# config_battery.net
KiCad netlist of a schematic drawn in Altium Designer
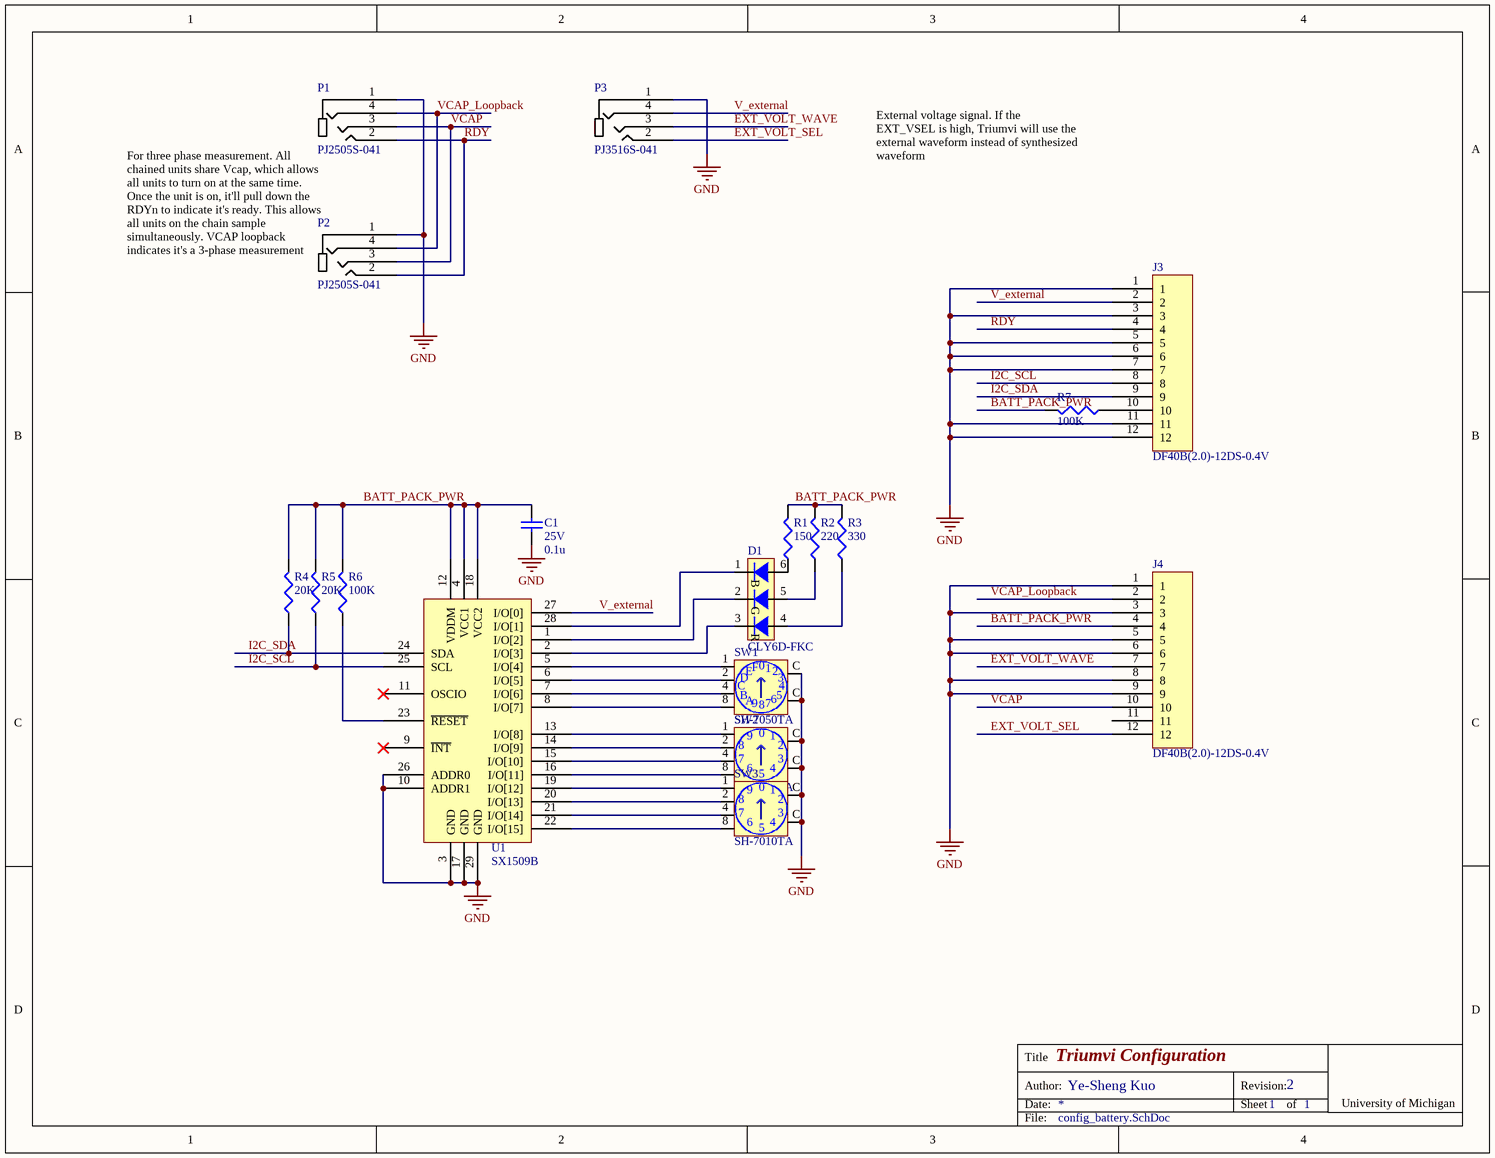
[diagram p0: config_battery.SchDoc]

(export (version "E")
  (design (tool "Eeschema 10.0.6"))
  (components
    (comp (ref "C1")
      (value "0.1u")
      (footprint "0603")
      (description "Ceramic capacitor, 0.1 uF, 0603 package")
      (fields
        (field (name "VOLTAGE RATED") "25V")
        (field (name "TOLERANCE") "10%")
        (field (name "Comment") "Ceramic capacitor")
      )
      (libsource (lib "rlc") (part "C_0.1u_25V_0603_ceramic"))
    )
    (comp (ref "D1")
      (value "CLY6D-FKC")
      (footprint "PLCC6")
      (description "CREE PLCC6 3 in 1 SMD LED")
      (libsource (lib "rlc") (part "D_CLY6D-FKC"))
    )
    (comp (ref "J3")
      (value "DF40B(2.0)-12DS-0.4V")
      (footprint "DF40B(2.0)-12DS-0.4V")
      (description "Hirose BM20 Series, 0.4mm pitch, 2mm stack height, 12 pos, header")
      (libsource (lib "connectors") (part "DF40B(2.0)-12DS-0.4V"))
    )
    (comp (ref "J4")
      (value "DF40B(2.0)-12DS-0.4V")
      (footprint "DF40B(2.0)-12DS-0.4V")
      (description "Hirose BM20 Series, 0.4mm pitch, 2mm stack height, 12 pos, header")
      (libsource (lib "connectors") (part "DF40B(2.0)-12DS-0.4V"))
    )
    (comp (ref "P1")
      (value "PJ2505S-041")
      (footprint "PJ2505S-041")
      (description "2.5 mm phone jack, 4 terminals")
      (libsource (lib "connectors") (part "PJ2505S-041"))
    )
    (comp (ref "P2")
      (value "PJ2505S-041")
      (footprint "PJ2505S-041")
      (description "2.5 mm phone jack, 4 terminals")
      (libsource (lib "connectors") (part "PJ2505S-041"))
    )
    (comp (ref "P3")
      (value "PJ3516S-041")
      (footprint "PJ3516S-041")
      (description "3.5 mm phone jack, 4 terminals")
      (libsource (lib "connectors") (part "PJ3516S-041"))
    )
    (comp (ref "R1")
      (value "150")
      (footprint "0603")
      (description "Chip resistor, 150,  0603 package")
      (fields (field (name "TOLERANCE") "1%") (field (name "POWER") "1/1 W"))
      (libsource (lib "rlc") (part "R_150_0603"))
    )
    (comp (ref "R2")
      (value "220")
      (footprint "0603")
      (description "Chip resistor, 220, 0603 package")
      (fields (field (name "TOLERANCE") "1%") (field (name "POWER") "1/10 W"))
      (libsource (lib "rlc") (part "R_220_0603"))
    )
    (comp (ref "R3")
      (value "330")
      (footprint "0603")
      (description "Chip resistor, 330, 0603 package")
      (fields (field (name "TOLERANCE") "1%") (field (name "POWER") "1/10 W"))
      (libsource (lib "rlc") (part "R_330_0603"))
    )
    (comp (ref "R4")
      (value "20K")
      (footprint "0603")
      (description "Chip resistor, 20K, 0603 package")
      (fields (field (name "TOLERANCE") "1%") (field (name "POWER") "1/10 W"))
      (libsource (lib "rlc") (part "R_20K_0603"))
    )
    (comp (ref "R5")
      (value "20K")
      (footprint "0603")
      (description "Chip resistor, 20K, 0603 package")
      (fields (field (name "TOLERANCE") "1%") (field (name "POWER") "1/10 W"))
      (libsource (lib "rlc") (part "R_20K_0603"))
    )
    (comp (ref "R6")
      (value "100K")
      (footprint "0603")
      (description "Chip resistor, 100K, 0603 package")
      (fields (field (name "TOLERANCE") "1%") (field (name "POWER") "1/10 W"))
      (libsource (lib "rlc") (part "R_100K_0603"))
    )
    (comp (ref "R7")
      (value "100K")
      (footprint "0603")
      (description "Chip resistor, 100K, 0603 package")
      (fields (field (name "TOLERANCE") "1%") (field (name "POWER") "1/10 W"))
      (libsource (lib "rlc") (part "R_100K_0603"))
    )
    (comp (ref "SW1")
      (value "SH-7050TA")
      (footprint "SH-7050A")
      (description "ROTARY CODED SWITCHES")
      (libsource (lib "switches") (part "SH-7050TA"))
    )
    (comp (ref "SW2")
      (value "SH-7010TA")
      (footprint "SH-7010A")
      (description "ROTARY CODED SWITCHES")
      (libsource (lib "switches") (part "SH-7010TA"))
    )
    (comp (ref "SW3")
      (value "SH-7010TA")
      (footprint "SH-7010A")
      (description "ROTARY CODED SWITCHES")
      (libsource (lib "switches") (part "SH-7010TA"))
    )
    (comp (ref "U1")
      (value "SX1509B")
      (footprint "QFN40P400X400X60_HS-29N")
      (description "Voltage Level Shifting GPIO  with LED Driver and Keypad Engine")
      (libsource (lib "io_expansion") (part "SX1509B"))
    )
  )
  (nets
    (net (code "1") (name "/BATT_PACK_PWR") (class "Default")
      (node (ref "C1") (pin "1") (pintype "passive"))
      (node (ref "J4") (pin "4") (pinfunction "4_4") (pintype "passive"))
      (node (ref "R1") (pin "1") (pintype "passive"))
      (node (ref "R2") (pin "1") (pintype "passive"))
      (node (ref "R3") (pin "1") (pintype "passive"))
      (node (ref "R4") (pin "1") (pintype "passive"))
      (node (ref "R5") (pin "1") (pintype "passive"))
      (node (ref "R6") (pin "1") (pintype "passive"))
      (node (ref "R7") (pin "1") (pintype "passive"))
      (node (ref "U1") (pin "12") (pinfunction "VDDM_12") (pintype "passive"))
      (node (ref "U1") (pin "18") (pinfunction "VCC2_18") (pintype "passive"))
      (node (ref "U1") (pin "4") (pinfunction "VCC1_4") (pintype "passive"))
    )
    (net (code "2") (name "/EXT_VOLT_SEL") (class "Default")
      (node (ref "J4") (pin "12") (pinfunction "12_12") (pintype "passive"))
      (node (ref "P3") (pin "2") (pinfunction "2_2") (pintype "passive"))
    )
    (net (code "3") (name "/EXT_VOLT_WAVE") (class "Default")
      (node (ref "J4") (pin "7") (pinfunction "7_7") (pintype "passive"))
      (node (ref "P3") (pin "3") (pinfunction "3_3") (pintype "passive"))
    )
    (net (code "4") (name "/I2C_SCL") (class "Default")
      (node (ref "J3") (pin "8") (pinfunction "8_8") (pintype "passive"))
      (node (ref "R5") (pin "2") (pintype "passive"))
      (node (ref "U1") (pin "25") (pinfunction "SCL_25") (pintype "passive"))
    )
    (net (code "5") (name "/I2C_SDA") (class "Default")
      (node (ref "J3") (pin "9") (pinfunction "9_9") (pintype "passive"))
      (node (ref "R4") (pin "2") (pintype "passive"))
      (node (ref "U1") (pin "24") (pinfunction "SDA_24") (pintype "passive"))
    )
    (net (code "6") (name "/VCAP") (class "Default")
      (node (ref "J4") (pin "10") (pinfunction "10_10") (pintype "passive"))
      (node (ref "P1") (pin "3") (pinfunction "3_3") (pintype "passive"))
      (node (ref "P2") (pin "3") (pinfunction "3_3") (pintype "passive"))
    )
    (net (code "7") (name "/VCAP_Loopback") (class "Default")
      (node (ref "J4") (pin "2") (pinfunction "2_2") (pintype "passive"))
      (node (ref "P1") (pin "4") (pinfunction "4_4") (pintype "passive"))
      (node (ref "P2") (pin "4") (pinfunction "4_4") (pintype "passive"))
    )
    (net (code "8") (name "/V_external") (class "Default")
      (node (ref "J3") (pin "2") (pinfunction "2_2") (pintype "passive"))
      (node (ref "P3") (pin "4") (pinfunction "4_4") (pintype "passive"))
      (node (ref "U1") (pin "27") (pinfunction "I/O[0]_27") (pintype "passive"))
    )
    (net (code "9") (name "/~{RDY}") (class "Default")
      (node (ref "J3") (pin "4") (pinfunction "4_4") (pintype "passive"))
      (node (ref "P1") (pin "2") (pinfunction "2_2") (pintype "passive"))
      (node (ref "P2") (pin "2") (pinfunction "2_2") (pintype "passive"))
    )
    (net (code "10") (name "GND") (class "Default")
      (node (ref "C1") (pin "2") (pintype "passive"))
      (node (ref "J3") (pin "1") (pinfunction "1_1") (pintype "passive"))
      (node (ref "J3") (pin "11") (pinfunction "11_11") (pintype "passive"))
      (node (ref "J3") (pin "12") (pinfunction "12_12") (pintype "passive"))
      (node (ref "J3") (pin "3") (pinfunction "3_3") (pintype "passive"))
      (node (ref "J3") (pin "5") (pinfunction "5_5") (pintype "passive"))
      (node (ref "J3") (pin "6") (pinfunction "6_6") (pintype "passive"))
      (node (ref "J3") (pin "7") (pinfunction "7_7") (pintype "passive"))
      (node (ref "J4") (pin "1") (pinfunction "1_1") (pintype "passive"))
      (node (ref "J4") (pin "3") (pinfunction "3_3") (pintype "passive"))
      (node (ref "J4") (pin "5") (pinfunction "5_5") (pintype "passive"))
      (node (ref "J4") (pin "6") (pinfunction "6_6") (pintype "passive"))
      (node (ref "J4") (pin "8") (pinfunction "8_8") (pintype "passive"))
      (node (ref "J4") (pin "9") (pinfunction "9_9") (pintype "passive"))
      (node (ref "P1") (pin "1") (pinfunction "1_1") (pintype "passive"))
      (node (ref "P2") (pin "1") (pinfunction "1_1") (pintype "passive"))
      (node (ref "P3") (pin "1") (pinfunction "1_1") (pintype "passive"))
      (node (ref "SW1") (pin "C") (pinfunction "C_C") (pintype "passive"))
      (node (ref "SW2") (pin "C") (pinfunction "C_C") (pintype "passive"))
      (node (ref "SW3") (pin "C") (pinfunction "C_C") (pintype "passive"))
      (node (ref "U1") (pin "10") (pinfunction "ADDR1_10") (pintype "passive"))
      (node (ref "U1") (pin "17") (pinfunction "GND_17") (pintype "passive"))
      (node (ref "U1") (pin "26") (pinfunction "ADDR0_26") (pintype "passive"))
      (node (ref "U1") (pin "29") (pinfunction "GND_29") (pintype "passive"))
      (node (ref "U1") (pin "3") (pinfunction "GND_3") (pintype "passive"))
    )
    (net (code "11") (name "Net-(D1-Pad4)") (class "Default")
      (node (ref "D1") (pin "4") (pinfunction "4_4") (pintype "passive"))
      (node (ref "R3") (pin "2") (pintype "passive"))
    )
    (net (code "12") (name "Net-(D1-Pad5)") (class "Default")
      (node (ref "D1") (pin "5") (pinfunction "5_5") (pintype "passive"))
      (node (ref "R2") (pin "2") (pintype "passive"))
    )
    (net (code "13") (name "Net-(D1-Pad6)") (class "Default")
      (node (ref "D1") (pin "6") (pinfunction "6_6") (pintype "passive"))
      (node (ref "R1") (pin "2") (pintype "passive"))
    )
    (net (code "14") (name "Net-(J3-Pad10)") (class "Default")
      (node (ref "J3") (pin "10") (pinfunction "10_10") (pintype "passive"))
      (node (ref "R7") (pin "2") (pintype "passive"))
    )
    (net (code "15") (name "Net-(U1-I{slash}O[1])") (class "Default")
      (node (ref "D1") (pin "1") (pintype "passive"))
      (node (ref "U1") (pin "28") (pinfunction "I/O[1]_28") (pintype "passive"))
    )
    (net (code "16") (name "Net-(U1-I{slash}O[2])") (class "Default")
      (node (ref "D1") (pin "2") (pintype "passive"))
      (node (ref "U1") (pin "1") (pinfunction "I/O[2]_1") (pintype "passive"))
    )
    (net (code "17") (name "Net-(U1-I{slash}O[3])") (class "Default")
      (node (ref "D1") (pin "3") (pinfunction "3_3") (pintype "passive"))
      (node (ref "U1") (pin "2") (pinfunction "I/O[3]_2") (pintype "passive"))
    )
    (net (code "18") (name "Net-(U1-I{slash}O[4])") (class "Default")
      (node (ref "SW1") (pin "1") (pinfunction "1_1") (pintype "passive"))
      (node (ref "U1") (pin "5") (pinfunction "I/O[4]_5") (pintype "passive"))
    )
    (net (code "19") (name "Net-(U1-I{slash}O[5])") (class "Default")
      (node (ref "SW1") (pin "2") (pinfunction "2_2") (pintype "passive"))
      (node (ref "U1") (pin "6") (pinfunction "I/O[5]_6") (pintype "passive"))
    )
    (net (code "20") (name "Net-(U1-I{slash}O[6])") (class "Default")
      (node (ref "SW1") (pin "4") (pinfunction "4_4") (pintype "passive"))
      (node (ref "U1") (pin "7") (pinfunction "I/O[6]_7") (pintype "passive"))
    )
    (net (code "21") (name "Net-(U1-I{slash}O[7])") (class "Default")
      (node (ref "SW1") (pin "8") (pinfunction "8_8") (pintype "passive"))
      (node (ref "U1") (pin "8") (pinfunction "I/O[7]_8") (pintype "passive"))
    )
    (net (code "22") (name "Net-(U1-I{slash}O[8])") (class "Default")
      (node (ref "SW2") (pin "1") (pinfunction "1_1") (pintype "passive"))
      (node (ref "U1") (pin "13") (pinfunction "I/O[8]_13") (pintype "passive"))
    )
    (net (code "23") (name "Net-(U1-I{slash}O[9])") (class "Default")
      (node (ref "SW2") (pin "2") (pinfunction "2_2") (pintype "passive"))
      (node (ref "U1") (pin "14") (pinfunction "I/O[9]_14") (pintype "passive"))
    )
    (net (code "24") (name "Net-(U1-I{slash}O[10])") (class "Default")
      (node (ref "SW2") (pin "4") (pinfunction "4_4") (pintype "passive"))
      (node (ref "U1") (pin "15") (pinfunction "I/O[10]_15") (pintype "passive"))
    )
    (net (code "25") (name "Net-(U1-I{slash}O[11])") (class "Default")
      (node (ref "SW2") (pin "8") (pinfunction "8_8") (pintype "passive"))
      (node (ref "U1") (pin "16") (pinfunction "I/O[11]_16") (pintype "passive"))
    )
    (net (code "26") (name "Net-(U1-I{slash}O[12])") (class "Default")
      (node (ref "SW3") (pin "1") (pinfunction "1_1") (pintype "passive"))
      (node (ref "U1") (pin "19") (pinfunction "I/O[12]_19") (pintype "passive"))
    )
    (net (code "27") (name "Net-(U1-I{slash}O[13])") (class "Default")
      (node (ref "SW3") (pin "2") (pinfunction "2_2") (pintype "passive"))
      (node (ref "U1") (pin "20") (pinfunction "I/O[13]_20") (pintype "passive"))
    )
    (net (code "28") (name "Net-(U1-I{slash}O[14])") (class "Default")
      (node (ref "SW3") (pin "4") (pinfunction "4_4") (pintype "passive"))
      (node (ref "U1") (pin "21") (pinfunction "I/O[14]_21") (pintype "passive"))
    )
    (net (code "29") (name "Net-(U1-I{slash}O[15])") (class "Default")
      (node (ref "SW3") (pin "8") (pinfunction "8_8") (pintype "passive"))
      (node (ref "U1") (pin "22") (pinfunction "I/O[15]_22") (pintype "passive"))
    )
    (net (code "30") (name "Net-(U1-~{RESET})") (class "Default")
      (node (ref "R6") (pin "2") (pintype "passive"))
      (node (ref "U1") (pin "23") (pinfunction "~{RESET}_23") (pintype "passive"))
    )
    (net (code "31") (name "unconnected-(J4-Pad11)") (class "Default")
      (node (ref "J4") (pin "11") (pinfunction "11_11") (pintype "passive"))
    )
    (net (code "32") (name "unconnected-(U1-OSCIO-Pad11)") (class "Default")
      (node (ref "U1") (pin "11") (pinfunction "OSCIO_11") (pintype "passive+no_connect"))
    )
    (net (code "33") (name "unconnected-(U1-~{INT}-Pad9)") (class "Default")
      (node (ref "U1") (pin "9") (pinfunction "~{INT}_9") (pintype "passive+no_connect"))
    )
  )
)
